# TCO_v1.net
KiCad netlist of a schematic drawn in EAGLE
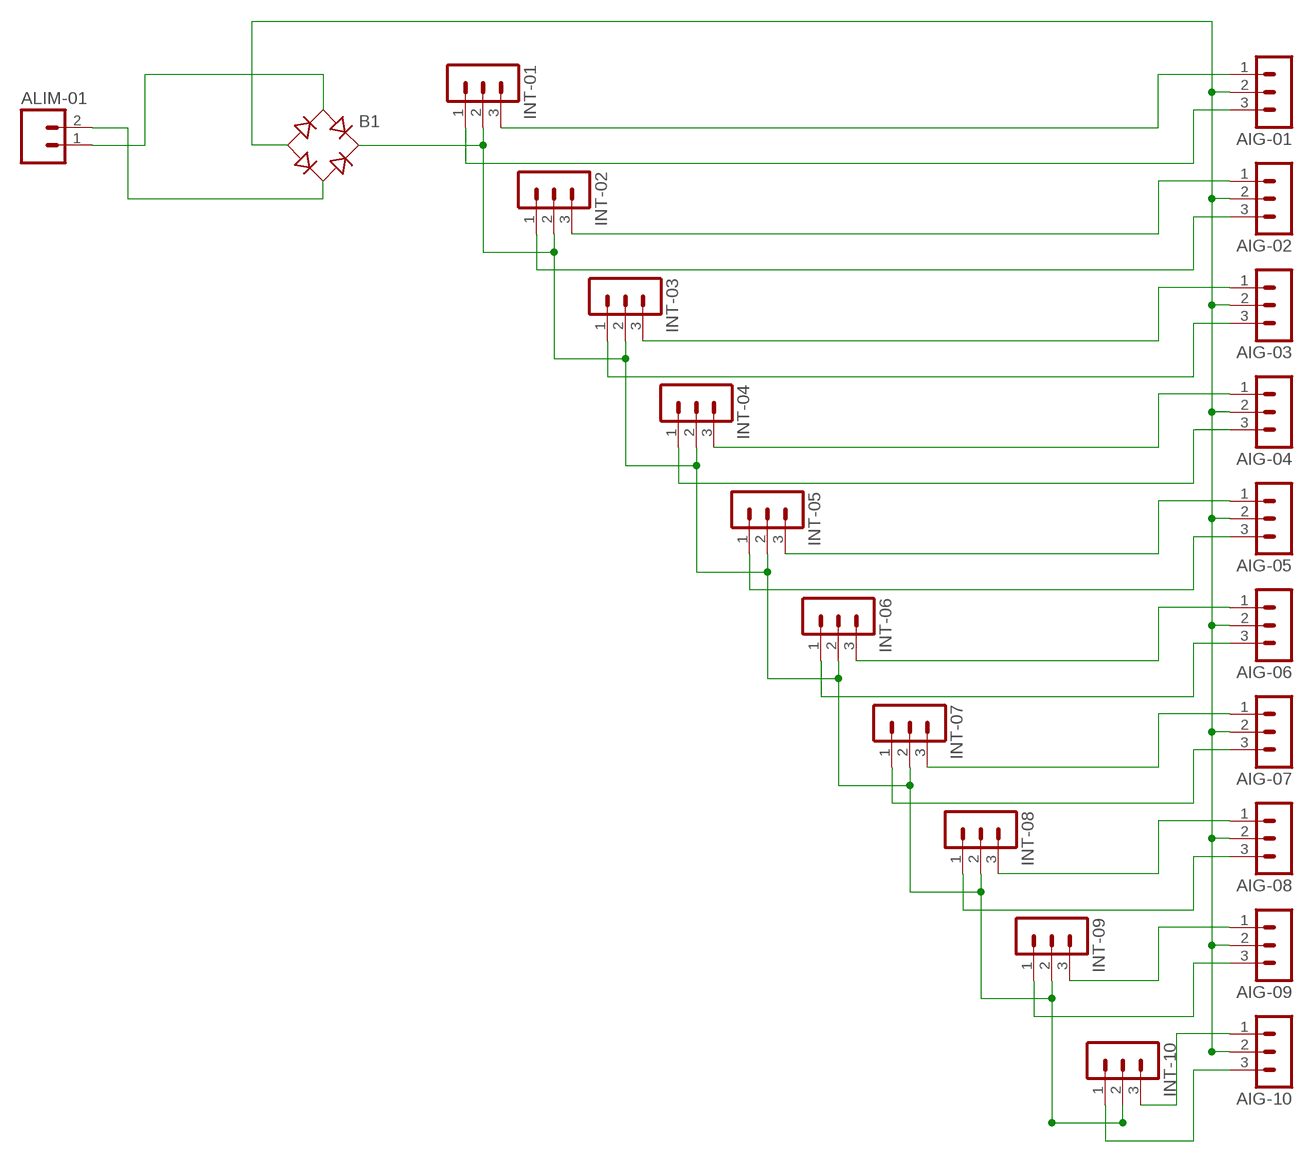
[diagram p0: schematic, sheet 1]

(export (version "E")
  (design (tool "Eeschema 10.0.6"))
  (components
    (comp (ref "AIG-01")
      (value "MA03-1")
      (footprint "eagle-import:MA03-1")
      (libsource (lib "eagle-import") (part "MA03-1"))
    )
    (comp (ref "AIG-02")
      (value "MA03-1")
      (footprint "eagle-import:MA03-1")
      (libsource (lib "eagle-import") (part "MA03-1"))
    )
    (comp (ref "AIG-03")
      (value "MA03-1")
      (footprint "eagle-import:MA03-1")
      (libsource (lib "eagle-import") (part "MA03-1"))
    )
    (comp (ref "AIG-04")
      (value "MA03-1")
      (footprint "eagle-import:MA03-1")
      (libsource (lib "eagle-import") (part "MA03-1"))
    )
    (comp (ref "AIG-05")
      (value "MA03-1")
      (footprint "eagle-import:MA03-1")
      (libsource (lib "eagle-import") (part "MA03-1"))
    )
    (comp (ref "AIG-06")
      (value "MA03-1")
      (footprint "eagle-import:MA03-1")
      (libsource (lib "eagle-import") (part "MA03-1"))
    )
    (comp (ref "AIG-07")
      (value "MA03-1")
      (footprint "eagle-import:MA03-1")
      (libsource (lib "eagle-import") (part "MA03-1"))
    )
    (comp (ref "AIG-08")
      (value "MA03-1")
      (footprint "eagle-import:MA03-1")
      (libsource (lib "eagle-import") (part "MA03-1"))
    )
    (comp (ref "AIG-09")
      (value "MA03-1")
      (footprint "eagle-import:MA03-1")
      (libsource (lib "eagle-import") (part "MA03-1"))
    )
    (comp (ref "AIG-10")
      (value "MA03-1")
      (footprint "eagle-import:MA03-1")
      (libsource (lib "eagle-import") (part "MA03-1"))
    )
    (comp (ref "ALIM-01")
      (value "M02")
      (footprint "eagle-import:02P")
      (libsource (lib "eagle-import") (part "M02"))
    )
    (comp (ref "B1")
      (value "B-DIL")
      (footprint "eagle-import:B-DIL")
      (libsource (lib "eagle-import") (part "B-DIL"))
    )
    (comp (ref "INT-01")
      (value "MA03-1")
      (footprint "eagle-import:MA03-1")
      (libsource (lib "eagle-import") (part "MA03-1"))
    )
    (comp (ref "INT-02")
      (value "MA03-1")
      (footprint "eagle-import:MA03-1")
      (libsource (lib "eagle-import") (part "MA03-1"))
    )
    (comp (ref "INT-03")
      (value "MA03-1")
      (footprint "eagle-import:MA03-1")
      (libsource (lib "eagle-import") (part "MA03-1"))
    )
    (comp (ref "INT-04")
      (value "MA03-1")
      (footprint "eagle-import:MA03-1")
      (libsource (lib "eagle-import") (part "MA03-1"))
    )
    (comp (ref "INT-05")
      (value "MA03-1")
      (footprint "eagle-import:MA03-1")
      (libsource (lib "eagle-import") (part "MA03-1"))
    )
    (comp (ref "INT-06")
      (value "MA03-1")
      (footprint "eagle-import:MA03-1")
      (libsource (lib "eagle-import") (part "MA03-1"))
    )
    (comp (ref "INT-07")
      (value "MA03-1")
      (footprint "eagle-import:MA03-1")
      (libsource (lib "eagle-import") (part "MA03-1"))
    )
    (comp (ref "INT-08")
      (value "MA03-1")
      (footprint "eagle-import:MA03-1")
      (libsource (lib "eagle-import") (part "MA03-1"))
    )
    (comp (ref "INT-09")
      (value "MA03-1")
      (footprint "eagle-import:MA03-1")
      (libsource (lib "eagle-import") (part "MA03-1"))
    )
    (comp (ref "INT-10")
      (value "MA03-1")
      (footprint "eagle-import:MA03-1")
      (libsource (lib "eagle-import") (part "MA03-1"))
    )
  )
  (nets
    (net (code "1") (name "Net-(AIG-01-Pad1)") (class "Default")
      (node (ref "AIG-01") (pin "1") (pinfunction "1_1") (pintype "passive"))
      (node (ref "INT-01") (pin "3") (pinfunction "3_3") (pintype "passive"))
    )
    (net (code "2") (name "Net-(AIG-01-Pad2)") (class "Default")
      (node (ref "AIG-01") (pin "2") (pinfunction "2_2") (pintype "passive"))
      (node (ref "AIG-02") (pin "2") (pinfunction "2_2") (pintype "passive"))
      (node (ref "AIG-03") (pin "2") (pinfunction "2_2") (pintype "passive"))
      (node (ref "AIG-04") (pin "2") (pinfunction "2_2") (pintype "passive"))
      (node (ref "AIG-05") (pin "2") (pinfunction "2_2") (pintype "passive"))
      (node (ref "AIG-06") (pin "2") (pinfunction "2_2") (pintype "passive"))
      (node (ref "AIG-07") (pin "2") (pinfunction "2_2") (pintype "passive"))
      (node (ref "AIG-08") (pin "2") (pinfunction "2_2") (pintype "passive"))
      (node (ref "AIG-09") (pin "2") (pinfunction "2_2") (pintype "passive"))
      (node (ref "AIG-10") (pin "2") (pinfunction "2_2") (pintype "passive"))
      (node (ref "B1") (pin "-") (pinfunction "-_-") (pintype "passive"))
    )
    (net (code "3") (name "Net-(AIG-01-Pad3)") (class "Default")
      (node (ref "AIG-01") (pin "3") (pinfunction "3_3") (pintype "passive"))
      (node (ref "INT-01") (pin "1") (pinfunction "1_1") (pintype "passive"))
    )
    (net (code "4") (name "Net-(AIG-02-Pad1)") (class "Default")
      (node (ref "AIG-02") (pin "1") (pinfunction "1_1") (pintype "passive"))
      (node (ref "INT-02") (pin "3") (pinfunction "3_3") (pintype "passive"))
    )
    (net (code "5") (name "Net-(AIG-02-Pad3)") (class "Default")
      (node (ref "AIG-02") (pin "3") (pinfunction "3_3") (pintype "passive"))
      (node (ref "INT-02") (pin "1") (pinfunction "1_1") (pintype "passive"))
    )
    (net (code "6") (name "Net-(AIG-03-Pad1)") (class "Default")
      (node (ref "AIG-03") (pin "1") (pinfunction "1_1") (pintype "passive"))
      (node (ref "INT-03") (pin "3") (pinfunction "3_3") (pintype "passive"))
    )
    (net (code "7") (name "Net-(AIG-03-Pad3)") (class "Default")
      (node (ref "AIG-03") (pin "3") (pinfunction "3_3") (pintype "passive"))
      (node (ref "INT-03") (pin "1") (pinfunction "1_1") (pintype "passive"))
    )
    (net (code "8") (name "Net-(AIG-04-Pad1)") (class "Default")
      (node (ref "AIG-04") (pin "1") (pinfunction "1_1") (pintype "passive"))
      (node (ref "INT-04") (pin "3") (pinfunction "3_3") (pintype "passive"))
    )
    (net (code "9") (name "Net-(AIG-04-Pad3)") (class "Default")
      (node (ref "AIG-04") (pin "3") (pinfunction "3_3") (pintype "passive"))
      (node (ref "INT-04") (pin "1") (pinfunction "1_1") (pintype "passive"))
    )
    (net (code "10") (name "Net-(AIG-05-Pad1)") (class "Default")
      (node (ref "AIG-05") (pin "1") (pinfunction "1_1") (pintype "passive"))
      (node (ref "INT-05") (pin "3") (pinfunction "3_3") (pintype "passive"))
    )
    (net (code "11") (name "Net-(AIG-05-Pad3)") (class "Default")
      (node (ref "AIG-05") (pin "3") (pinfunction "3_3") (pintype "passive"))
      (node (ref "INT-05") (pin "1") (pinfunction "1_1") (pintype "passive"))
    )
    (net (code "12") (name "Net-(AIG-06-Pad1)") (class "Default")
      (node (ref "AIG-06") (pin "1") (pinfunction "1_1") (pintype "passive"))
      (node (ref "INT-06") (pin "3") (pinfunction "3_3") (pintype "passive"))
    )
    (net (code "13") (name "Net-(AIG-06-Pad3)") (class "Default")
      (node (ref "AIG-06") (pin "3") (pinfunction "3_3") (pintype "passive"))
      (node (ref "INT-06") (pin "1") (pinfunction "1_1") (pintype "passive"))
    )
    (net (code "14") (name "Net-(AIG-07-Pad1)") (class "Default")
      (node (ref "AIG-07") (pin "1") (pinfunction "1_1") (pintype "passive"))
      (node (ref "INT-07") (pin "3") (pinfunction "3_3") (pintype "passive"))
    )
    (net (code "15") (name "Net-(AIG-07-Pad3)") (class "Default")
      (node (ref "AIG-07") (pin "3") (pinfunction "3_3") (pintype "passive"))
      (node (ref "INT-07") (pin "1") (pinfunction "1_1") (pintype "passive"))
    )
    (net (code "16") (name "Net-(AIG-08-Pad1)") (class "Default")
      (node (ref "AIG-08") (pin "1") (pinfunction "1_1") (pintype "passive"))
      (node (ref "INT-08") (pin "3") (pinfunction "3_3") (pintype "passive"))
    )
    (net (code "17") (name "Net-(AIG-08-Pad3)") (class "Default")
      (node (ref "AIG-08") (pin "3") (pinfunction "3_3") (pintype "passive"))
      (node (ref "INT-08") (pin "1") (pinfunction "1_1") (pintype "passive"))
    )
    (net (code "18") (name "Net-(AIG-09-Pad1)") (class "Default")
      (node (ref "AIG-09") (pin "1") (pinfunction "1_1") (pintype "passive"))
      (node (ref "INT-09") (pin "3") (pinfunction "3_3") (pintype "passive"))
    )
    (net (code "19") (name "Net-(AIG-09-Pad3)") (class "Default")
      (node (ref "AIG-09") (pin "3") (pinfunction "3_3") (pintype "passive"))
      (node (ref "INT-09") (pin "1") (pinfunction "1_1") (pintype "passive"))
    )
    (net (code "20") (name "Net-(AIG-10-Pad1)") (class "Default")
      (node (ref "AIG-10") (pin "1") (pinfunction "1_1") (pintype "passive"))
      (node (ref "INT-10") (pin "3") (pinfunction "3_3") (pintype "passive"))
    )
    (net (code "21") (name "Net-(AIG-10-Pad3)") (class "Default")
      (node (ref "AIG-10") (pin "3") (pinfunction "3_3") (pintype "passive"))
      (node (ref "INT-10") (pin "1") (pinfunction "1_1") (pintype "passive"))
    )
    (net (code "22") (name "Net-(ALIM-01-Pad1)") (class "Default")
      (node (ref "ALIM-01") (pin "1") (pinfunction "1_1") (pintype "passive"))
      (node (ref "B1") (pin "AC1") (pinfunction "AC1_AC1") (pintype "passive"))
    )
    (net (code "23") (name "Net-(ALIM-01-Pad2)") (class "Default")
      (node (ref "ALIM-01") (pin "2") (pinfunction "2_2") (pintype "passive"))
      (node (ref "B1") (pin "AC2") (pinfunction "AC2_AC2") (pintype "passive"))
    )
    (net (code "24") (name "Net-(B1-Pad+)") (class "Default")
      (node (ref "B1") (pin "+") (pinfunction "+_+") (pintype "passive"))
      (node (ref "INT-01") (pin "2") (pinfunction "2_2") (pintype "passive"))
      (node (ref "INT-02") (pin "2") (pinfunction "2_2") (pintype "passive"))
      (node (ref "INT-03") (pin "2") (pinfunction "2_2") (pintype "passive"))
      (node (ref "INT-04") (pin "2") (pinfunction "2_2") (pintype "passive"))
      (node (ref "INT-05") (pin "2") (pinfunction "2_2") (pintype "passive"))
      (node (ref "INT-06") (pin "2") (pinfunction "2_2") (pintype "passive"))
      (node (ref "INT-07") (pin "2") (pinfunction "2_2") (pintype "passive"))
      (node (ref "INT-08") (pin "2") (pinfunction "2_2") (pintype "passive"))
      (node (ref "INT-09") (pin "2") (pinfunction "2_2") (pintype "passive"))
      (node (ref "INT-10") (pin "2") (pinfunction "2_2") (pintype "passive"))
    )
  )
)
